# usb_debug.net
KiCad netlist of a schematic drawn in Altium Designer
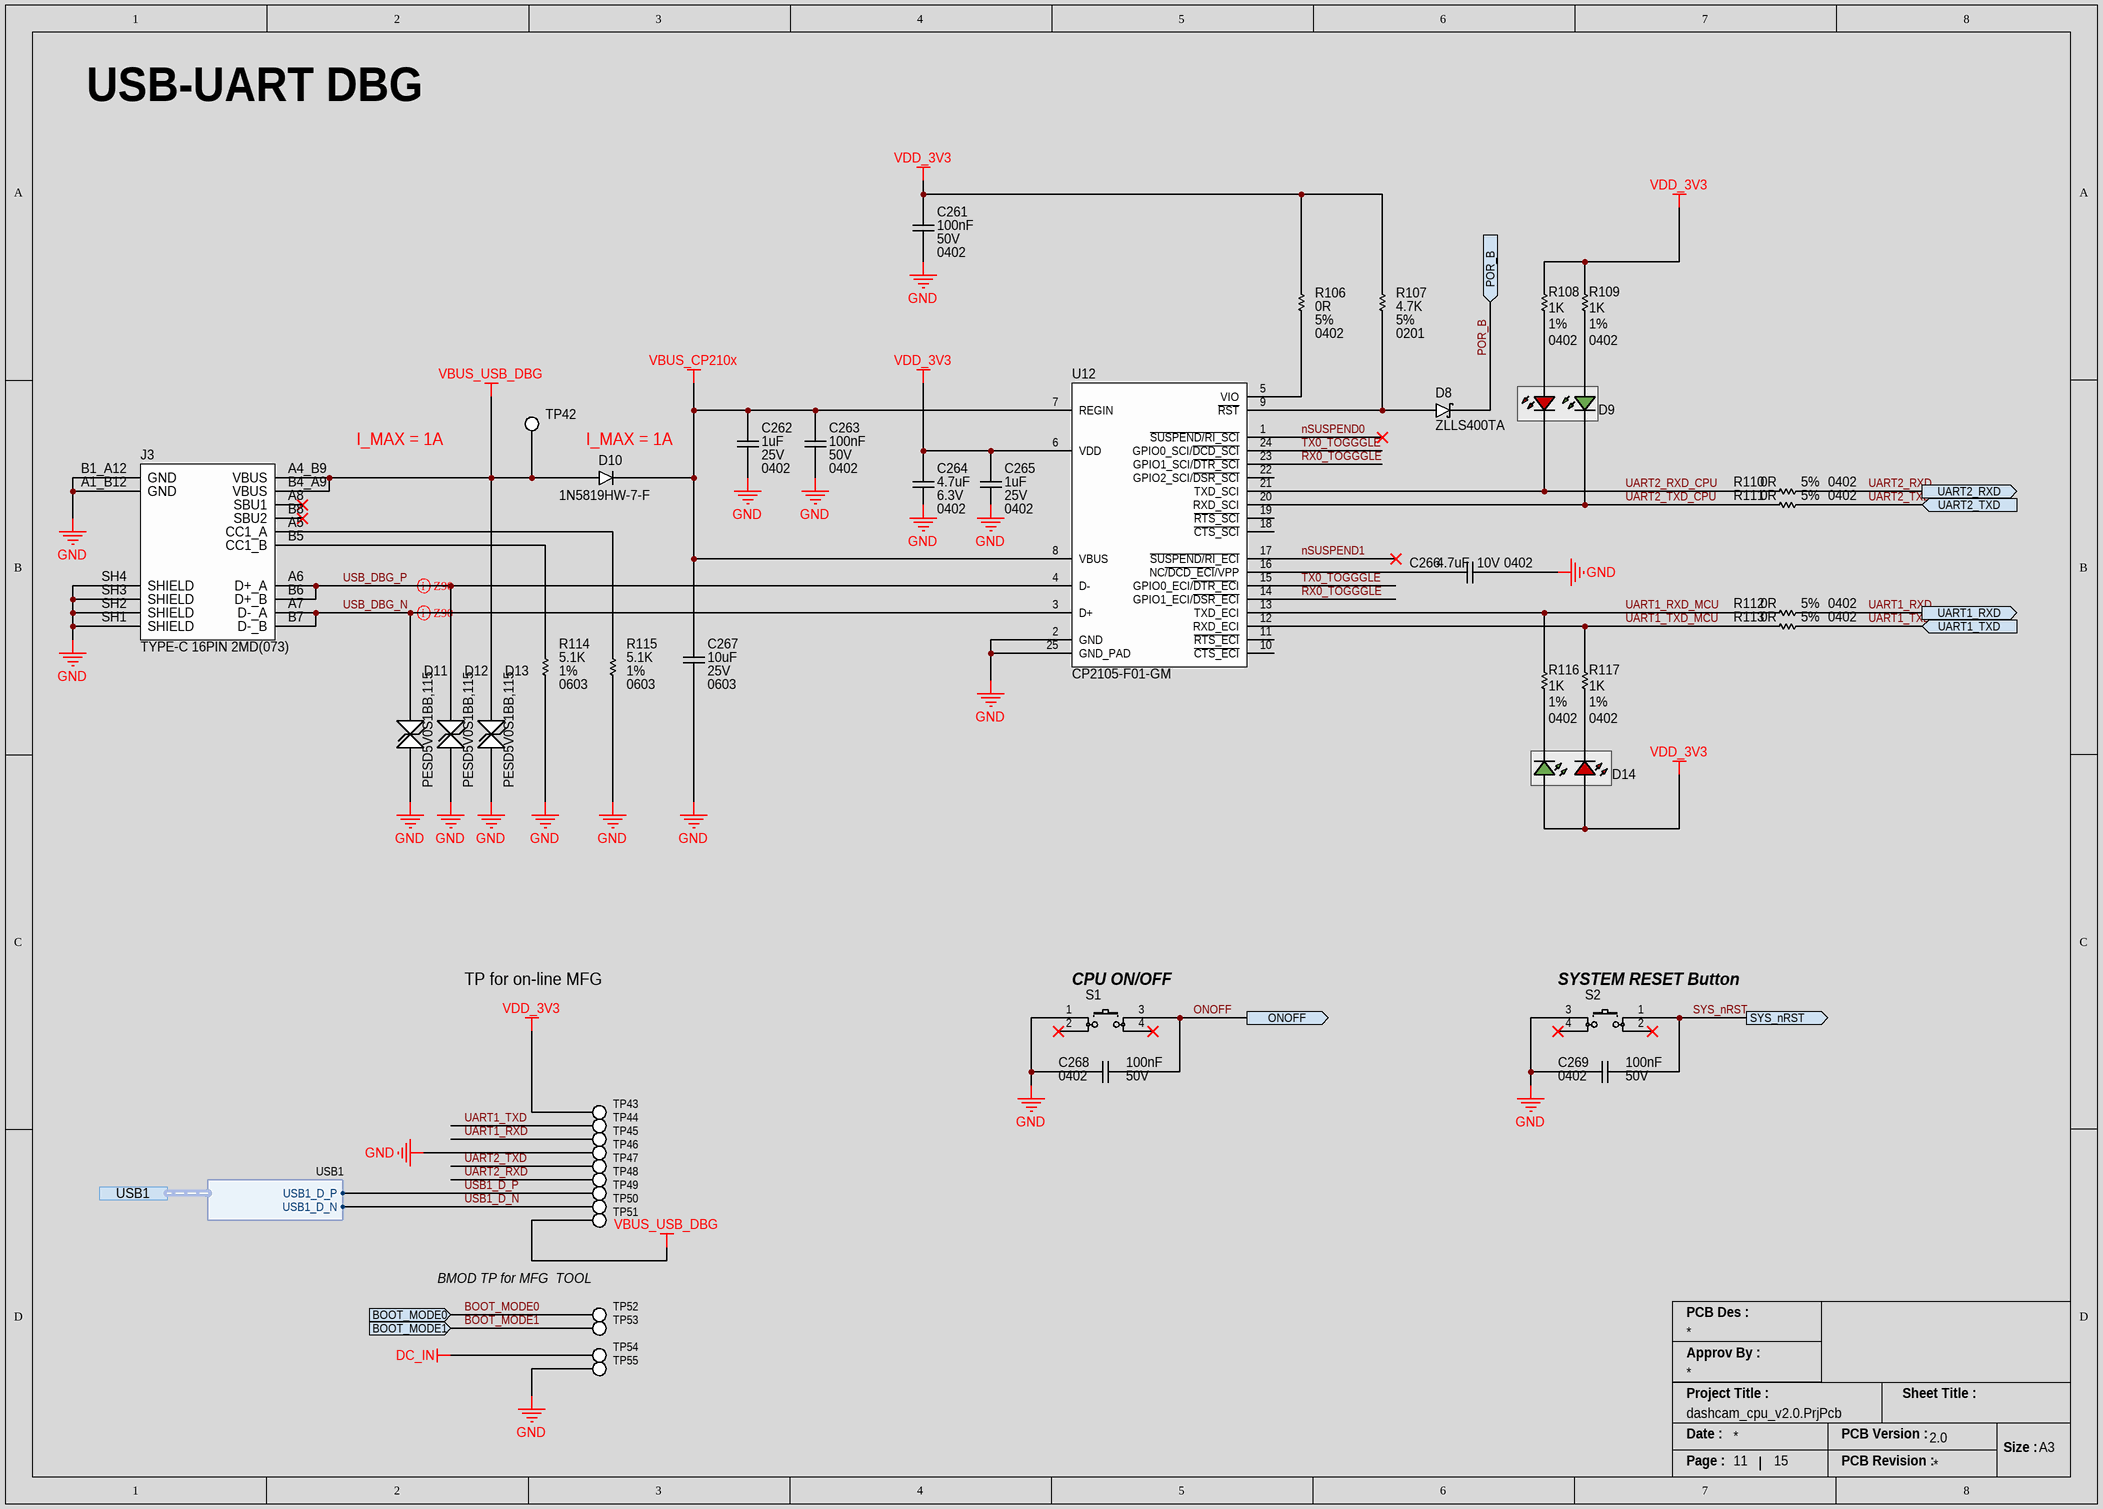
[diagram p0: usb_debug.SchDoc]

(export (version "E")
  (design (tool "Eeschema 10.0.6"))
  (components
    (comp (ref "C261")
      (value "GRM155R71H104KE14D")
      (footprint "CAP_0402_CAPC1005X05N")
      (description "Multilayer Ceramic Capacitor, 0.1 uF, 16 V, ± 10%, X7R, 0402 [1005 Metric]")
      (fields
        (field (name "MANUFACTURER") "Murata")
        (field (name "TOLERANCE") "10%")
        (field (name "VOLTAGE RATING") "50V")
        (field (name "CAPACITANCE") "100nF")
        (field (name "CASE/PACKAGE") "0402")
      )
      (libsource (lib "Electronic Devices_LIB") (part "CAP_100NF_50V_X7R_0402"))
    )
    (comp (ref "C262")
      (value "GRM155R61E105KA12D")
      (footprint "CAP_0402_CAPC1005X05N")
      (description "Multilayer Ceramic Capacitor, 1 uF, 25 V, ± 10%, X5R, 0402 [1005 Metric]")
      (fields
        (field (name "MANUFACTURER") "Murata")
        (field (name "TOLERANCE") "10%")
        (field (name "VOLTAGE RATING") "25V")
        (field (name "CAPACITANCE") "1uF")
        (field (name "CASE CODE (IMPERIAL)") "0402")
      )
      (libsource (lib "Electronic Devices_LIB") (part "CAP_1UF_25V_X5R_0402"))
    )
    (comp (ref "C263")
      (value "GRM155R71H104KE14D")
      (footprint "CAP_0402_CAPC1005X05N")
      (description "Multilayer Ceramic Capacitor, 0.1 uF, 16 V, ± 10%, X7R, 0402 [1005 Metric]")
      (fields
        (field (name "MANUFACTURER") "Murata")
        (field (name "TOLERANCE") "10%")
        (field (name "VOLTAGE RATING") "50V")
        (field (name "CAPACITANCE") "100nF")
        (field (name "CASE/PACKAGE") "0402")
      )
      (libsource (lib "Electronic Devices_LIB") (part "CAP_100NF_50V_X7R_0402"))
    )
    (comp (ref "C264")
      (value "C1005X5R0J475M050BC")
      (footprint "CAP_0402_CAPC1005X05N")
      (description "Multilayer Ceramic Capacitor, 4.7 uF, 6.3 V, ± 20%, X5R, 0402 [1005 Metric]")
      (fields
        (field (name "MANUFACTURER") "TDK")
        (field (name "TOLERANCE") "20%")
        (field (name "CAPACITANCE") "4.7uF")
        (field (name "VOLTAGE RATING") "6.3V")
        (field (name "CASE/PACKAGE") "0402")
      )
      (libsource (lib "Electronic Devices_LIB") (part "CAP_4.7UF_6.3V_X5R_0402"))
    )
    (comp (ref "C265")
      (value "GRM155R61E105KA12D")
      (footprint "CAP_0402_CAPC1005X05N")
      (description "Multilayer Ceramic Capacitor, 1 uF, 25 V, ± 10%, X5R, 0402 [1005 Metric]")
      (fields
        (field (name "MANUFACTURER") "Murata")
        (field (name "TOLERANCE") "10%")
        (field (name "VOLTAGE RATING") "25V")
        (field (name "CAPACITANCE") "1uF")
        (field (name "CASE CODE (IMPERIAL)") "0402")
      )
      (libsource (lib "Electronic Devices_LIB") (part "CAP_1UF_25V_X5R_0402"))
    )
    (comp (ref "C266")
      (value "CL05A475KP5NRNC")
      (footprint "CAP_0402_CAPC1005X05N")
      (description "Multilayer Ceramic Capacitor, 4.7 uF, 10 V, ± 10%, X5R, 0402 [1005 Metric]")
      (fields
        (field (name "MANUFACTURER") "Samsung")
        (field (name "TOLERANCE") "10%")
        (field (name "CAPACITANCE") "4.7uF")
        (field (name "VOLTAGE RATING") "10V")
        (field (name "CASE/PACKAGE") "0402")
      )
      (libsource (lib "Electronic Devices_LIB") (part "CAP_4.7UF_10V_X5R_0402"))
    )
    (comp (ref "C267")
      (value "GRM188R61E106MA73D")
      (footprint "CAP_0603_CAPC1608X08N")
      (description "Multilayer Ceramic Capacitor, 10 uF, 25 V, ± 20%, X5R, 0603 [1608 Metric]")
      (fields
        (field (name "MANUFACTURER") "Murata")
        (field (name "TOLERANCE") "20%")
        (field (name "CASE/PACKAGE") "0603")
        (field (name "CAPACITANCE") "10uF")
        (field (name "VOLTAGE RATING") "25V")
      )
      (libsource (lib "Electronic Devices_LIB") (part "CAP_10UF_25V_X5R_0603"))
    )
    (comp (ref "C268")
      (value "GRM155R71H104KE14D")
      (footprint "CAP_0402_CAPC1005X05N")
      (description "Multilayer Ceramic Capacitor, 0.1 uF, 16 V, ± 10%, X7R, 0402 [1005 Metric]")
      (fields
        (field (name "MANUFACTURER") "Murata")
        (field (name "TOLERANCE") "10%")
        (field (name "VOLTAGE RATING") "50V")
        (field (name "CAPACITANCE") "100nF")
        (field (name "CASE/PACKAGE") "0402")
      )
      (libsource (lib "Electronic Devices_LIB") (part "CAP_100NF_50V_X7R_0402"))
    )
    (comp (ref "C269")
      (value "GRM155R71H104KE14D")
      (footprint "CAP_0402_CAPC1005X05N")
      (description "Multilayer Ceramic Capacitor, 0.1 uF, 16 V, ± 10%, X7R, 0402 [1005 Metric]")
      (fields
        (field (name "MANUFACTURER") "Murata")
        (field (name "TOLERANCE") "10%")
        (field (name "VOLTAGE RATING") "50V")
        (field (name "CAPACITANCE") "100nF")
        (field (name "CASE/PACKAGE") "0402")
      )
      (libsource (lib "Electronic Devices_LIB") (part "CAP_100NF_50V_X7R_0402"))
    )
    (comp (ref "D8")
      (value "ZLLS400TA")
      (footprint "DIO_SOD2512X113N")
      (description "DIODE SCHOTTKY 40V 520MA SOD323")
      (fields (field (name "MANUFACTURER") "Diodes Zetex"))
      (libsource (lib "Electronic Devices_LIB") (part "DIO_SCTKY_40V_520mA_ZLLS400TA"))
    )
    (comp (ref "D9")
      (value "LTST-C195KGJRKT")
      (footprint "DIO_LED0606_LTST-C195")
      (description "LED GREEN/RED CLEAR 0606 SMD")
      (fields (field (name "MANUFACTURER") "Vishay Lite-On"))
      (libsource (lib "") (part "LED_DIO_BICOLOR_LTST-C195KGJRKT_1"))
    )
    (comp (ref "D10")
      (value "1N5819HW-7-F")
      (footprint "DIO_SOD3716X145N")
      (description "Rectifier Diode, Schottky, 1 Phase, 1 Element, 1A, 40V V(RRM), Silicon")
      (fields (field (name "MANUFACTURER") "Diodes"))
      (libsource (lib "Electronic Devices_LIB") (part "DIO_RECT_40V_1A_1N5819HW-7-F"))
    )
    (comp (ref "D11")
      (value "PESD5V0S1BB,115")
      (footprint "DIO_TVS_SODFL1608X65N")
      (description "ESD Suppressor Diode TVS Bi-Dir 5V Automotive 2-Pin SOD-523 T/R / TVS DIODE 5VWM 14VC SOD523")
      (fields (field (name "MANUFACTURER") "Nexperia"))
      (libsource (lib "Electronic Devices_LIB") (part "DIO_TVS_BID_5V_PESD5V0S1BB,115"))
    )
    (comp (ref "D12")
      (value "PESD5V0S1BB,115")
      (footprint "DIO_TVS_SODFL1608X65N")
      (description "ESD Suppressor Diode TVS Bi-Dir 5V Automotive 2-Pin SOD-523 T/R / TVS DIODE 5VWM 14VC SOD523")
      (fields (field (name "MANUFACTURER") "Nexperia"))
      (libsource (lib "Electronic Devices_LIB") (part "DIO_TVS_BID_5V_PESD5V0S1BB,115"))
    )
    (comp (ref "D13")
      (value "PESD5V0S1BB,115")
      (footprint "DIO_TVS_SODFL1608X65N")
      (description "ESD Suppressor Diode TVS Bi-Dir 5V Automotive 2-Pin SOD-523 T/R / TVS DIODE 5VWM 14VC SOD523")
      (fields (field (name "MANUFACTURER") "Nexperia"))
      (libsource (lib "Electronic Devices_LIB") (part "DIO_TVS_BID_5V_PESD5V0S1BB,115"))
    )
    (comp (ref "D14")
      (value "LTST-C195KGJRKT")
      (footprint "DIO_LED0606_LTST-C195")
      (description "LED GREEN/RED CLEAR 0606 SMD")
      (fields (field (name "MANUFACTURER") "Vishay Lite-On"))
      (libsource (lib "Electronic Devices_LIB") (part "LED_DIO_BICOLOR_LTST-C195KGJRKT"))
    )
    (comp (ref "J3")
      (value "TYPE-C 16PIN 2MD(073)")
      (footprint "CONN_USB_C_16P")
      (description "5A 1 Surface Mount 16P Female -25℃~+85℃ Type-C SMD USB Connectors ROHS")
      (fields (field (name "MANUFACTURER") "SHOU HAN"))
      (libsource (lib "Electronic Devices_LIB") (part "CONN_USB_TYPEC_2.0_16P_TYPE-C 16PIN 2MD(073)"))
    )
    (comp (ref "R106")
      (value "ERJ-2GE0R00X")
      (footprint "RES_0402_RESC1005X04N")
      (description "SMD Chip Resistor, Jumper, 0 ohm, 100 mW, 0402 [1005 Metric], Thick Film, General Purpose")
      (fields
        (field (name "MANUFACTURER") "Panasonic")
        (field (name "CASE CODE (IMPERIAL)") "0402")
        (field (name "TOLERANCE") "5%")
        (field (name "RESISTANCE") "0R")
      )
      (libsource (lib "Electronic Devices_LIB") (part "RES_0R_5%_100mW_0402"))
    )
    (comp (ref "R107")
      (value "RK73B1HTTC472J")
      (footprint "RES_0201_RESC0603X02N")
      (description "Res Thick Film 0201 4.7K Ohm 5% 0.05W(1/20W) ±200ppm/C Pad SMD Automotive T/R")
      (fields
        (field (name "MANUFACTURER") "KOA Speer")
        (field (name "TOLERANCE") "5%")
        (field (name "RESISTANCE") "4.7K")
        (field (name "CASE/PACKAGE") "0201")
      )
      (libsource (lib "Electronic Devices_LIB") (part "RES_4.7K_5%_50mW_0201"))
    )
    (comp (ref "R108")
      (value "ERJ-2RKF1001X")
      (footprint "RES_0402_RESC1005X04N")
      (description "RES SMD 1K OHM 1% 1/10W 0402")
      (fields
        (field (name "MANUFACTURER") "Panasonic")
        (field (name "RESISTANCE") "1K")
        (field (name "TOLERANCE") "1%")
        (field (name "CASE/PACKAGE") "0402")
      )
      (libsource (lib "Electronic Devices_LIB") (part "RES_1K_1%_100mW_0402"))
    )
    (comp (ref "R109")
      (value "ERJ-2RKF1001X")
      (footprint "RES_0402_RESC1005X04N")
      (description "RES SMD 1K OHM 1% 1/10W 0402")
      (fields
        (field (name "MANUFACTURER") "Panasonic")
        (field (name "RESISTANCE") "1K")
        (field (name "TOLERANCE") "1%")
        (field (name "CASE/PACKAGE") "0402")
      )
      (libsource (lib "Electronic Devices_LIB") (part "RES_1K_1%_100mW_0402"))
    )
    (comp (ref "R110")
      (value "ERJ-2GE0R00X")
      (footprint "RES_0402_RESC1005X04N")
      (description "SMD Chip Resistor, Jumper, 0 ohm, 100 mW, 0402 [1005 Metric], Thick Film, General Purpose")
      (fields
        (field (name "MANUFACTURER") "Panasonic")
        (field (name "CASE CODE (IMPERIAL)") "0402")
        (field (name "TOLERANCE") "5%")
        (field (name "RESISTANCE") "0R")
      )
      (libsource (lib "Electronic Devices_LIB") (part "RES_0R_5%_100mW_0402"))
    )
    (comp (ref "R111")
      (value "ERJ-2GE0R00X")
      (footprint "RES_0402_RESC1005X04N")
      (description "SMD Chip Resistor, Jumper, 0 ohm, 100 mW, 0402 [1005 Metric], Thick Film, General Purpose")
      (fields
        (field (name "MANUFACTURER") "Panasonic")
        (field (name "CASE CODE (IMPERIAL)") "0402")
        (field (name "TOLERANCE") "5%")
        (field (name "RESISTANCE") "0R")
      )
      (libsource (lib "Electronic Devices_LIB") (part "RES_0R_5%_100mW_0402"))
    )
    (comp (ref "R112")
      (value "ERJ-2GE0R00X")
      (footprint "RES_0402_RESC1005X04N")
      (description "SMD Chip Resistor, Jumper, 0 ohm, 100 mW, 0402 [1005 Metric], Thick Film, General Purpose")
      (fields
        (field (name "MANUFACTURER") "Panasonic")
        (field (name "CASE CODE (IMPERIAL)") "0402")
        (field (name "TOLERANCE") "5%")
        (field (name "RESISTANCE") "0R")
      )
      (libsource (lib "Electronic Devices_LIB") (part "RES_0R_5%_100mW_0402"))
    )
    (comp (ref "R113")
      (value "ERJ-2GE0R00X")
      (footprint "RES_0402_RESC1005X04N")
      (description "SMD Chip Resistor, Jumper, 0 ohm, 100 mW, 0402 [1005 Metric], Thick Film, General Purpose")
      (fields
        (field (name "MANUFACTURER") "Panasonic")
        (field (name "CASE CODE (IMPERIAL)") "0402")
        (field (name "TOLERANCE") "5%")
        (field (name "RESISTANCE") "0R")
      )
      (libsource (lib "Electronic Devices_LIB") (part "RES_0R_5%_100mW_0402"))
    )
    (comp (ref "R114")
      (value "RC0603FR-075K1L")
      (footprint "RES_0603_RESC1608X04N")
      (description "SMD Chip Resistor, 5.1 kOhm, ± 1%, 100 mW, 0603 [1608 Metric], Thick Film, General Purpose")
      (fields
        (field (name "MANUFACTURER") "Yageo")
        (field (name "TOLERANCE") "1%")
        (field (name "RESISTANCE") "5.1K")
        (field (name "CASE/PACKAGE") "0603")
      )
      (libsource (lib "Electronic Devices_LIB") (part "RES_5.1K_1%_100mW_0603"))
    )
    (comp (ref "R115")
      (value "RC0603FR-075K1L")
      (footprint "RES_0603_RESC1608X04N")
      (description "SMD Chip Resistor, 5.1 kOhm, ± 1%, 100 mW, 0603 [1608 Metric], Thick Film, General Purpose")
      (fields
        (field (name "MANUFACTURER") "Yageo")
        (field (name "TOLERANCE") "1%")
        (field (name "RESISTANCE") "5.1K")
        (field (name "CASE/PACKAGE") "0603")
      )
      (libsource (lib "Electronic Devices_LIB") (part "RES_5.1K_1%_100mW_0603"))
    )
    (comp (ref "R116")
      (value "ERJ-2RKF1001X")
      (footprint "RES_0402_RESC1005X04N")
      (description "RES SMD 1K OHM 1% 1/10W 0402")
      (fields
        (field (name "MANUFACTURER") "Panasonic")
        (field (name "RESISTANCE") "1K")
        (field (name "TOLERANCE") "1%")
        (field (name "CASE/PACKAGE") "0402")
      )
      (libsource (lib "Electronic Devices_LIB") (part "RES_1K_1%_100mW_0402"))
    )
    (comp (ref "R117")
      (value "ERJ-2RKF1001X")
      (footprint "RES_0402_RESC1005X04N")
      (description "RES SMD 1K OHM 1% 1/10W 0402")
      (fields
        (field (name "MANUFACTURER") "Panasonic")
        (field (name "RESISTANCE") "1K")
        (field (name "TOLERANCE") "1%")
        (field (name "CASE/PACKAGE") "0402")
      )
      (libsource (lib "Electronic Devices_LIB") (part "RES_1K_1%_100mW_0402"))
    )
    (comp (ref "S1")
      (value "PTS526SK15SMTR2LFS")
      (footprint "SWT_NO_PTS526SK15SMTR2LFS")
      (description "Switch Tactile N.O. SPST Round Button Gull Wing 0.05A 12VDC 200000Cycles 2.55N SMD T/R")
      (fields (field (name "MANUFACTURER") "ITT C&K"))
      (libsource (lib "Electronic Devices_LIB") (part "SWITCH_NO_SPST_0.05A"))
    )
    (comp (ref "S2")
      (value "PTS526SK15SMTR2LFS")
      (footprint "SWT_NO_PTS526SK15SMTR2LFS")
      (description "Switch Tactile N.O. SPST Round Button Gull Wing 0.05A 12VDC 200000Cycles 2.55N SMD T/R")
      (fields (field (name "MANUFACTURER") "ITT C&K"))
      (libsource (lib "Electronic Devices_LIB") (part "SWITCH_NO_SPST_0.05A"))
    )
    (comp (ref "TP42")
      (value "NO COMPONENT")
      (footprint "TP_PAD_1.6MM_SMD_ROUND")
      (description "Test Point, SMD pad, round, 1.5mm, 1.6mm, 3mm diameter")
      (libsource (lib "Electronic Devices_LIB") (part "TP_PAD_SMD_Round"))
    )
    (comp (ref "TP43")
      (value "NO COMPONENT")
      (footprint "TP_PAD_1.6MM_SMD_ROUND")
      (description "Test Point, SMD pad, round, 1.5mm, 1.6mm, 3mm diameter")
      (libsource (lib "Electronic Devices_LIB") (part "TP_PAD_SMD_Round"))
    )
    (comp (ref "TP44")
      (value "NO COMPONENT")
      (footprint "TP_PAD_1.6MM_SMD_ROUND")
      (description "Test Point, SMD pad, round, 1.5mm, 1.6mm, 3mm diameter")
      (libsource (lib "Electronic Devices_LIB") (part "TP_PAD_SMD_Round"))
    )
    (comp (ref "TP45")
      (value "NO COMPONENT")
      (footprint "TP_PAD_1.6MM_SMD_ROUND")
      (description "Test Point, SMD pad, round, 1.5mm, 1.6mm, 3mm diameter")
      (libsource (lib "Electronic Devices_LIB") (part "TP_PAD_SMD_Round"))
    )
    (comp (ref "TP46")
      (value "NO COMPONENT")
      (footprint "TP_PAD_1.6MM_SMD_ROUND")
      (description "Test Point, SMD pad, round, 1.5mm, 1.6mm, 3mm diameter")
      (libsource (lib "Electronic Devices_LIB") (part "TP_PAD_SMD_Round"))
    )
    (comp (ref "TP47")
      (value "NO COMPONENT")
      (footprint "TP_PAD_1.6MM_SMD_ROUND")
      (description "Test Point, SMD pad, round, 1.5mm, 1.6mm, 3mm diameter")
      (libsource (lib "Electronic Devices_LIB") (part "TP_PAD_SMD_Round"))
    )
    (comp (ref "TP48")
      (value "NO COMPONENT")
      (footprint "TP_PAD_1.6MM_SMD_ROUND")
      (description "Test Point, SMD pad, round, 1.5mm, 1.6mm, 3mm diameter")
      (libsource (lib "Electronic Devices_LIB") (part "TP_PAD_SMD_Round"))
    )
    (comp (ref "TP49")
      (value "NO COMPONENT")
      (footprint "TP_PAD_1.6MM_SMD_ROUND")
      (description "Test Point, SMD pad, round, 1.5mm, 1.6mm, 3mm diameter")
      (libsource (lib "Electronic Devices_LIB") (part "TP_PAD_SMD_Round"))
    )
    (comp (ref "TP50")
      (value "NO COMPONENT")
      (footprint "TP_PAD_1.6MM_SMD_ROUND")
      (description "Test Point, SMD pad, round, 1.5mm, 1.6mm, 3mm diameter")
      (libsource (lib "Electronic Devices_LIB") (part "TP_PAD_SMD_Round"))
    )
    (comp (ref "TP51")
      (value "NO COMPONENT")
      (footprint "TP_PAD_1.6MM_SMD_ROUND")
      (description "Test Point, SMD pad, round, 1.5mm, 1.6mm, 3mm diameter")
      (libsource (lib "Electronic Devices_LIB") (part "TP_PAD_SMD_Round"))
    )
    (comp (ref "TP52")
      (value "NO COMPONENT")
      (footprint "TP_PAD_1.6MM_SMD_ROUND")
      (description "Test Point, SMD pad, round, 1.5mm, 1.6mm, 3mm diameter")
      (libsource (lib "Electronic Devices_LIB") (part "TP_PAD_SMD_Round"))
    )
    (comp (ref "TP53")
      (value "NO COMPONENT")
      (footprint "TP_PAD_1.6MM_SMD_ROUND")
      (description "Test Point, SMD pad, round, 1.5mm, 1.6mm, 3mm diameter")
      (libsource (lib "Electronic Devices_LIB") (part "TP_PAD_SMD_Round"))
    )
    (comp (ref "TP54")
      (value "NO COMPONENT")
      (footprint "TP_PAD_1.6MM_SMD_ROUND")
      (description "Test Point, SMD pad, round, 1.5mm, 1.6mm, 3mm diameter")
      (libsource (lib "Electronic Devices_LIB") (part "TP_PAD_SMD_Round"))
    )
    (comp (ref "TP55")
      (value "NO COMPONENT")
      (footprint "TP_PAD_1.6MM_SMD_ROUND")
      (description "Test Point, SMD pad, round, 1.5mm, 1.6mm, 3mm diameter")
      (libsource (lib "Electronic Devices_LIB") (part "TP_PAD_SMD_Round"))
    )
    (comp (ref "U12")
      (value "CP2105-F01-GM")
      (footprint "IC_USB_UART_QFN50P400X400X80-25N-D")
      (description "IC SGL USB-DL UART BRIDGE 24QFN")
      (fields (field (name "MANUFACTURER") "Silicon Labs"))
      (libsource (lib "Electronic Devices_LIB") (part "IC_USB_UART_CP2105-F01-GM"))
    )
  )
  (nets
    (net (code "2") (name "/BOOT_MODE0") (class "Default")
      (node (ref "TP52") (pin "1") (pinfunction "1_1") (pintype "passive"))
    )
    (net (code "3") (name "/BOOT_MODE1") (class "Default")
      (node (ref "TP53") (pin "1") (pinfunction "1_1") (pintype "passive"))
    )
    (net (code "4") (name "/ONOFF") (class "Default")
      (node (ref "C268") (pin "1") (pinfunction "1_1") (pintype "passive"))
      (node (ref "S1") (pin "3") (pinfunction "NO1_3") (pintype "passive"))
    )
    (net (code "5") (name "/POR_B") (class "Default")
      (node (ref "D8") (pin "1") (pinfunction "K_1") (pintype "passive"))
    )
    (net (code "6") (name "/RX0_TOGGGLE") (class "Default")
      (node (ref "U12") (pin "14") (pinfunction "GPIO1_ECI/~{DSR_ECI}_14") (pintype "passive"))
      (node (ref "U12") (pin "23") (pinfunction "GPIO1_SCI/~{DTR_SCI}_23") (pintype "passive"))
    )
    (net (code "7") (name "/SYS_nRST") (class "Default")
      (node (ref "C269") (pin "1") (pinfunction "1_1") (pintype "passive"))
      (node (ref "S2") (pin "1") (pinfunction "COM_1_1") (pintype "passive"))
    )
    (net (code "8") (name "/TX0_TOGGGLE") (class "Default")
      (node (ref "U12") (pin "15") (pinfunction "GPIO0_ECI/~{DTR_EC}I_15") (pintype "passive"))
      (node (ref "U12") (pin "24") (pinfunction "GPIO0_SCI/~{DCD_SCI}_24") (pintype "passive"))
    )
    (net (code "9") (name "/UART1_RXD") (class "Default")
      (node (ref "R112") (pin "2") (pinfunction "2_2") (pintype "passive"))
      (node (ref "TP45") (pin "1") (pinfunction "1_1") (pintype "passive"))
    )
    (net (code "10") (name "/UART1_RXD_MCU") (class "Default")
      (node (ref "R112") (pin "1") (pinfunction "1_1") (pintype "passive"))
      (node (ref "R116") (pin "2") (pinfunction "2_2") (pintype "passive"))
      (node (ref "U12") (pin "13") (pinfunction "TXD_ECI_13") (pintype "passive"))
    )
    (net (code "11") (name "/UART1_TXD") (class "Default")
      (node (ref "R113") (pin "2") (pinfunction "2_2") (pintype "passive"))
      (node (ref "TP44") (pin "1") (pinfunction "1_1") (pintype "passive"))
    )
    (net (code "12") (name "/UART1_TXD_MCU") (class "Default")
      (node (ref "R113") (pin "1") (pinfunction "1_1") (pintype "passive"))
      (node (ref "R117") (pin "2") (pinfunction "2_2") (pintype "passive"))
      (node (ref "U12") (pin "12") (pinfunction "RXD_ECI_12") (pintype "passive"))
    )
    (net (code "13") (name "/UART2_RXD") (class "Default")
      (node (ref "R110") (pin "2") (pinfunction "2_2") (pintype "passive"))
      (node (ref "TP48") (pin "1") (pinfunction "1_1") (pintype "passive"))
    )
    (net (code "14") (name "/UART2_RXD_CPU") (class "Default")
      (node (ref "D9") (pin "4") (pinfunction "K1_4") (pintype "passive"))
      (node (ref "R110") (pin "1") (pinfunction "1_1") (pintype "passive"))
      (node (ref "U12") (pin "21") (pinfunction "TXD_SCI_21") (pintype "passive"))
    )
    (net (code "15") (name "/UART2_TXD") (class "Default")
      (node (ref "R111") (pin "2") (pinfunction "2_2") (pintype "passive"))
      (node (ref "TP47") (pin "1") (pinfunction "1_1") (pintype "passive"))
    )
    (net (code "16") (name "/UART2_TXD_CPU") (class "Default")
      (node (ref "D9") (pin "3") (pinfunction "K1_3") (pintype "passive"))
      (node (ref "R111") (pin "1") (pinfunction "1_1") (pintype "passive"))
      (node (ref "U12") (pin "20") (pinfunction "RXD_SCI_20") (pintype "passive"))
    )
    (net (code "17") (name "/USB1_D_N") (class "Default")
      (node (ref "TP50") (pin "1") (pinfunction "1_1") (pintype "passive"))
    )
    (net (code "18") (name "/USB1_D_P") (class "Default")
      (node (ref "TP49") (pin "1") (pinfunction "1_1") (pintype "passive"))
    )
    (net (code "19") (name "/USB_DBG_N") (class "Default")
      (node (ref "D11") (pin "2") (pinfunction "K2_2") (pintype "passive"))
      (node (ref "J3") (pin "A7") (pinfunction "D-_A_A7") (pintype "passive"))
      (node (ref "J3") (pin "B7") (pinfunction "D-_B_B7") (pintype "passive"))
      (node (ref "U12") (pin "3") (pinfunction "D+_3") (pintype "passive"))
    )
    (net (code "20") (name "/USB_DBG_P") (class "Default")
      (node (ref "D12") (pin "2") (pinfunction "K2_2") (pintype "passive"))
      (node (ref "J3") (pin "A6") (pinfunction "D+_A_A6") (pintype "passive"))
      (node (ref "J3") (pin "B6") (pinfunction "D+_B_B6") (pintype "passive"))
      (node (ref "U12") (pin "4") (pinfunction "D-_4") (pintype "passive"))
    )
    (net (code "21") (name "/nSUSPEND0") (class "Default")
      (node (ref "U12") (pin "1") (pinfunction "~{SUSPEND/RI_SCI}_1") (pintype "passive+no_connect"))
    )
    (net (code "22") (name "/nSUSPEND1") (class "Default")
      (node (ref "U12") (pin "17") (pinfunction "~{SUSPEND/RI_ECI}_17") (pintype "passive+no_connect"))
    )
    (net (code "24") (name "DC_IN") (class "Default")
      (node (ref "TP54") (pin "1") (pinfunction "1_1") (pintype "passive"))
    )
    (net (code "25") (name "GND") (class "Default")
      (node (ref "C261") (pin "1") (pinfunction "1_1") (pintype "passive"))
      (node (ref "C262") (pin "1") (pinfunction "1_1") (pintype "passive"))
      (node (ref "C263") (pin "1") (pinfunction "1_1") (pintype "passive"))
      (node (ref "C264") (pin "1") (pinfunction "1_1") (pintype "passive"))
      (node (ref "C265") (pin "1") (pinfunction "1_1") (pintype "passive"))
      (node (ref "C266") (pin "2") (pinfunction "2_2") (pintype "passive"))
      (node (ref "C267") (pin "1") (pinfunction "1_1") (pintype "passive"))
      (node (ref "C268") (pin "2") (pinfunction "2_2") (pintype "passive"))
      (node (ref "C269") (pin "2") (pinfunction "2_2") (pintype "passive"))
      (node (ref "D11") (pin "1") (pinfunction "K1_1") (pintype "passive"))
      (node (ref "D12") (pin "1") (pinfunction "K1_1") (pintype "passive"))
      (node (ref "D13") (pin "1") (pinfunction "K1_1") (pintype "passive"))
      (node (ref "J3") (pin "A1_B12") (pinfunction "GND_A1_B12") (pintype "power_in"))
      (node (ref "J3") (pin "B1_A12") (pinfunction "GND_B1_A12") (pintype "power_in"))
      (node (ref "J3") (pin "SH1") (pinfunction "SHIELD_SH1") (pintype "passive"))
      (node (ref "J3") (pin "SH2") (pinfunction "SHIELD_SH2") (pintype "passive"))
      (node (ref "J3") (pin "SH3") (pinfunction "SHIELD_SH3") (pintype "passive"))
      (node (ref "J3") (pin "SH4") (pinfunction "SHIELD_SH4") (pintype "passive"))
      (node (ref "R114") (pin "1") (pinfunction "1_1") (pintype "passive"))
      (node (ref "R115") (pin "1") (pinfunction "1_1") (pintype "passive"))
      (node (ref "S1") (pin "1") (pinfunction "COM_1_1") (pintype "passive"))
      (node (ref "S2") (pin "3") (pinfunction "NO1_3") (pintype "passive"))
      (node (ref "TP46") (pin "1") (pinfunction "1_1") (pintype "passive"))
      (node (ref "TP55") (pin "1") (pinfunction "1_1") (pintype "passive"))
      (node (ref "U12") (pin "2") (pinfunction "GND_2") (pintype "passive"))
      (node (ref "U12") (pin "25") (pinfunction "GND_PAD_25") (pintype "passive"))
    )
    (net (code "26") (name "Net-(D8-A)") (class "Default")
      (node (ref "D8") (pin "2") (pinfunction "A_2") (pintype "passive"))
      (node (ref "R107") (pin "1") (pinfunction "1_1") (pintype "passive"))
      (node (ref "U12") (pin "9") (pinfunction "~{RST}_9") (pintype "passive"))
    )
    (net (code "27") (name "Net-(D9-A1)") (class "Default")
      (node (ref "D9") (pin "1") (pinfunction "A1_1") (pintype "passive"))
      (node (ref "R109") (pin "1") (pinfunction "1_1") (pintype "passive"))
    )
    (net (code "28") (name "Net-(D9-A2)") (class "Default")
      (node (ref "D9") (pin "2") (pinfunction "A2_2") (pintype "passive"))
      (node (ref "R108") (pin "1") (pinfunction "1_1") (pintype "passive"))
    )
    (net (code "29") (name "Net-(D14-K1-Pad3)") (class "Default")
      (node (ref "D14") (pin "3") (pinfunction "K1_3") (pintype "passive"))
      (node (ref "R116") (pin "1") (pinfunction "1_1") (pintype "passive"))
    )
    (net (code "30") (name "Net-(D14-K1-Pad4)") (class "Default")
      (node (ref "D14") (pin "4") (pinfunction "K1_4") (pintype "passive"))
      (node (ref "R117") (pin "1") (pinfunction "1_1") (pintype "passive"))
    )
    (net (code "31") (name "Net-(J3-CC1_A)") (class "Default")
      (node (ref "J3") (pin "A5") (pinfunction "CC1_A_A5") (pintype "passive"))
      (node (ref "R115") (pin "2") (pinfunction "2_2") (pintype "passive"))
    )
    (net (code "32") (name "Net-(J3-CC1_B)") (class "Default")
      (node (ref "J3") (pin "B5") (pinfunction "CC1_B_B5") (pintype "passive"))
      (node (ref "R114") (pin "2") (pinfunction "2_2") (pintype "passive"))
    )
    (net (code "33") (name "Net-(U12-NC~{{slash}DCD_ECI}{slash}VPP)") (class "Default")
      (node (ref "C266") (pin "1") (pinfunction "1_1") (pintype "passive"))
      (node (ref "U12") (pin "16") (pinfunction "NC~{/DCD_ECI}/VPP_16") (pintype "passive"))
    )
    (net (code "34") (name "Net-(U12-VIO)") (class "Default")
      (node (ref "R106") (pin "1") (pinfunction "1_1") (pintype "passive"))
      (node (ref "U12") (pin "5") (pinfunction "VIO_5") (pintype "passive"))
    )
    (net (code "35") (name "VBUS_CP210x") (class "Default")
      (node (ref "C262") (pin "2") (pinfunction "2_2") (pintype "passive"))
      (node (ref "C263") (pin "2") (pinfunction "2_2") (pintype "passive"))
      (node (ref "C267") (pin "2") (pinfunction "2_2") (pintype "passive"))
      (node (ref "D10") (pin "1") (pinfunction "K_1") (pintype "passive"))
      (node (ref "U12") (pin "7") (pinfunction "REGIN_7") (pintype "passive"))
      (node (ref "U12") (pin "8") (pinfunction "VBUS_8") (pintype "passive"))
    )
    (net (code "36") (name "VBUS_USB_DBG") (class "Default")
      (node (ref "D10") (pin "2") (pinfunction "A_2") (pintype "passive"))
      (node (ref "D13") (pin "2") (pinfunction "K2_2") (pintype "passive"))
      (node (ref "J3") (pin "A4_B9") (pinfunction "VBUS_A4_B9") (pintype "power_in"))
      (node (ref "J3") (pin "B4_A9") (pinfunction "VBUS_B4_A9") (pintype "power_in"))
      (node (ref "TP42") (pin "1") (pinfunction "1_1") (pintype "passive"))
      (node (ref "TP51") (pin "1") (pinfunction "1_1") (pintype "passive"))
    )
    (net (code "37") (name "VDD_3V3") (class "Default")
      (node (ref "C261") (pin "2") (pinfunction "2_2") (pintype "passive"))
      (node (ref "C264") (pin "2") (pinfunction "2_2") (pintype "passive"))
      (node (ref "C265") (pin "2") (pinfunction "2_2") (pintype "passive"))
      (node (ref "D14") (pin "1") (pinfunction "A1_1") (pintype "passive"))
      (node (ref "D14") (pin "2") (pinfunction "A2_2") (pintype "passive"))
      (node (ref "R106") (pin "2") (pinfunction "2_2") (pintype "passive"))
      (node (ref "R107") (pin "2") (pinfunction "2_2") (pintype "passive"))
      (node (ref "R108") (pin "2") (pinfunction "2_2") (pintype "passive"))
      (node (ref "R109") (pin "2") (pinfunction "2_2") (pintype "passive"))
      (node (ref "TP43") (pin "1") (pinfunction "1_1") (pintype "passive"))
      (node (ref "U12") (pin "6") (pinfunction "VDD_6") (pintype "passive"))
    )
    (net (code "38") (name "unconnected-(J3-SBU1-PadA8)") (class "Default")
      (node (ref "J3") (pin "A8") (pinfunction "SBU1_A8") (pintype "passive+no_connect"))
    )
    (net (code "39") (name "unconnected-(J3-SBU2-PadB8)") (class "Default")
      (node (ref "J3") (pin "B8") (pinfunction "SBU2_B8") (pintype "passive+no_connect"))
    )
    (net (code "40") (name "unconnected-(S1-COM2-Pad2)") (class "Default")
      (node (ref "S1") (pin "2") (pinfunction "COM2_2") (pintype "passive+no_connect"))
    )
    (net (code "41") (name "unconnected-(S1-NO2-Pad4)") (class "Default")
      (node (ref "S1") (pin "4") (pinfunction "NO2_4") (pintype "passive+no_connect"))
    )
    (net (code "42") (name "unconnected-(S2-COM2-Pad2)") (class "Default")
      (node (ref "S2") (pin "2") (pinfunction "COM2_2") (pintype "passive+no_connect"))
    )
    (net (code "43") (name "unconnected-(S2-NO2-Pad4)") (class "Default")
      (node (ref "S2") (pin "4") (pinfunction "NO2_4") (pintype "passive+no_connect"))
    )
    (net (code "44") (name "unconnected-(U12-GPIO2_SCI{slash}~{DSR_SCI}-Pad22)") (class "Default")
      (node (ref "U12") (pin "22") (pinfunction "GPIO2_SCI/~{DSR_SCI}_22") (pintype "passive"))
    )
    (net (code "45") (name "unconnected-(U12-~{CTS_ECI}-Pad10)") (class "Default")
      (node (ref "U12") (pin "10") (pinfunction "~{CTS_ECI}_10") (pintype "passive"))
    )
    (net (code "46") (name "unconnected-(U12-~{CTS_SCI}-Pad18)") (class "Default")
      (node (ref "U12") (pin "18") (pinfunction "~{CTS_SCI}_18") (pintype "passive"))
    )
    (net (code "47") (name "unconnected-(U12-~{RTS_ECI}-Pad11)") (class "Default")
      (node (ref "U12") (pin "11") (pinfunction "~{RTS_ECI}_11") (pintype "passive"))
    )
    (net (code "48") (name "unconnected-(U12-~{RTS_SCI}-Pad19)") (class "Default")
      (node (ref "U12") (pin "19") (pinfunction "~{RTS_SCI}_19") (pintype "passive"))
    )
  )
)
